# batteryCharger.net
KiCad netlist of a schematic drawn in EAGLE
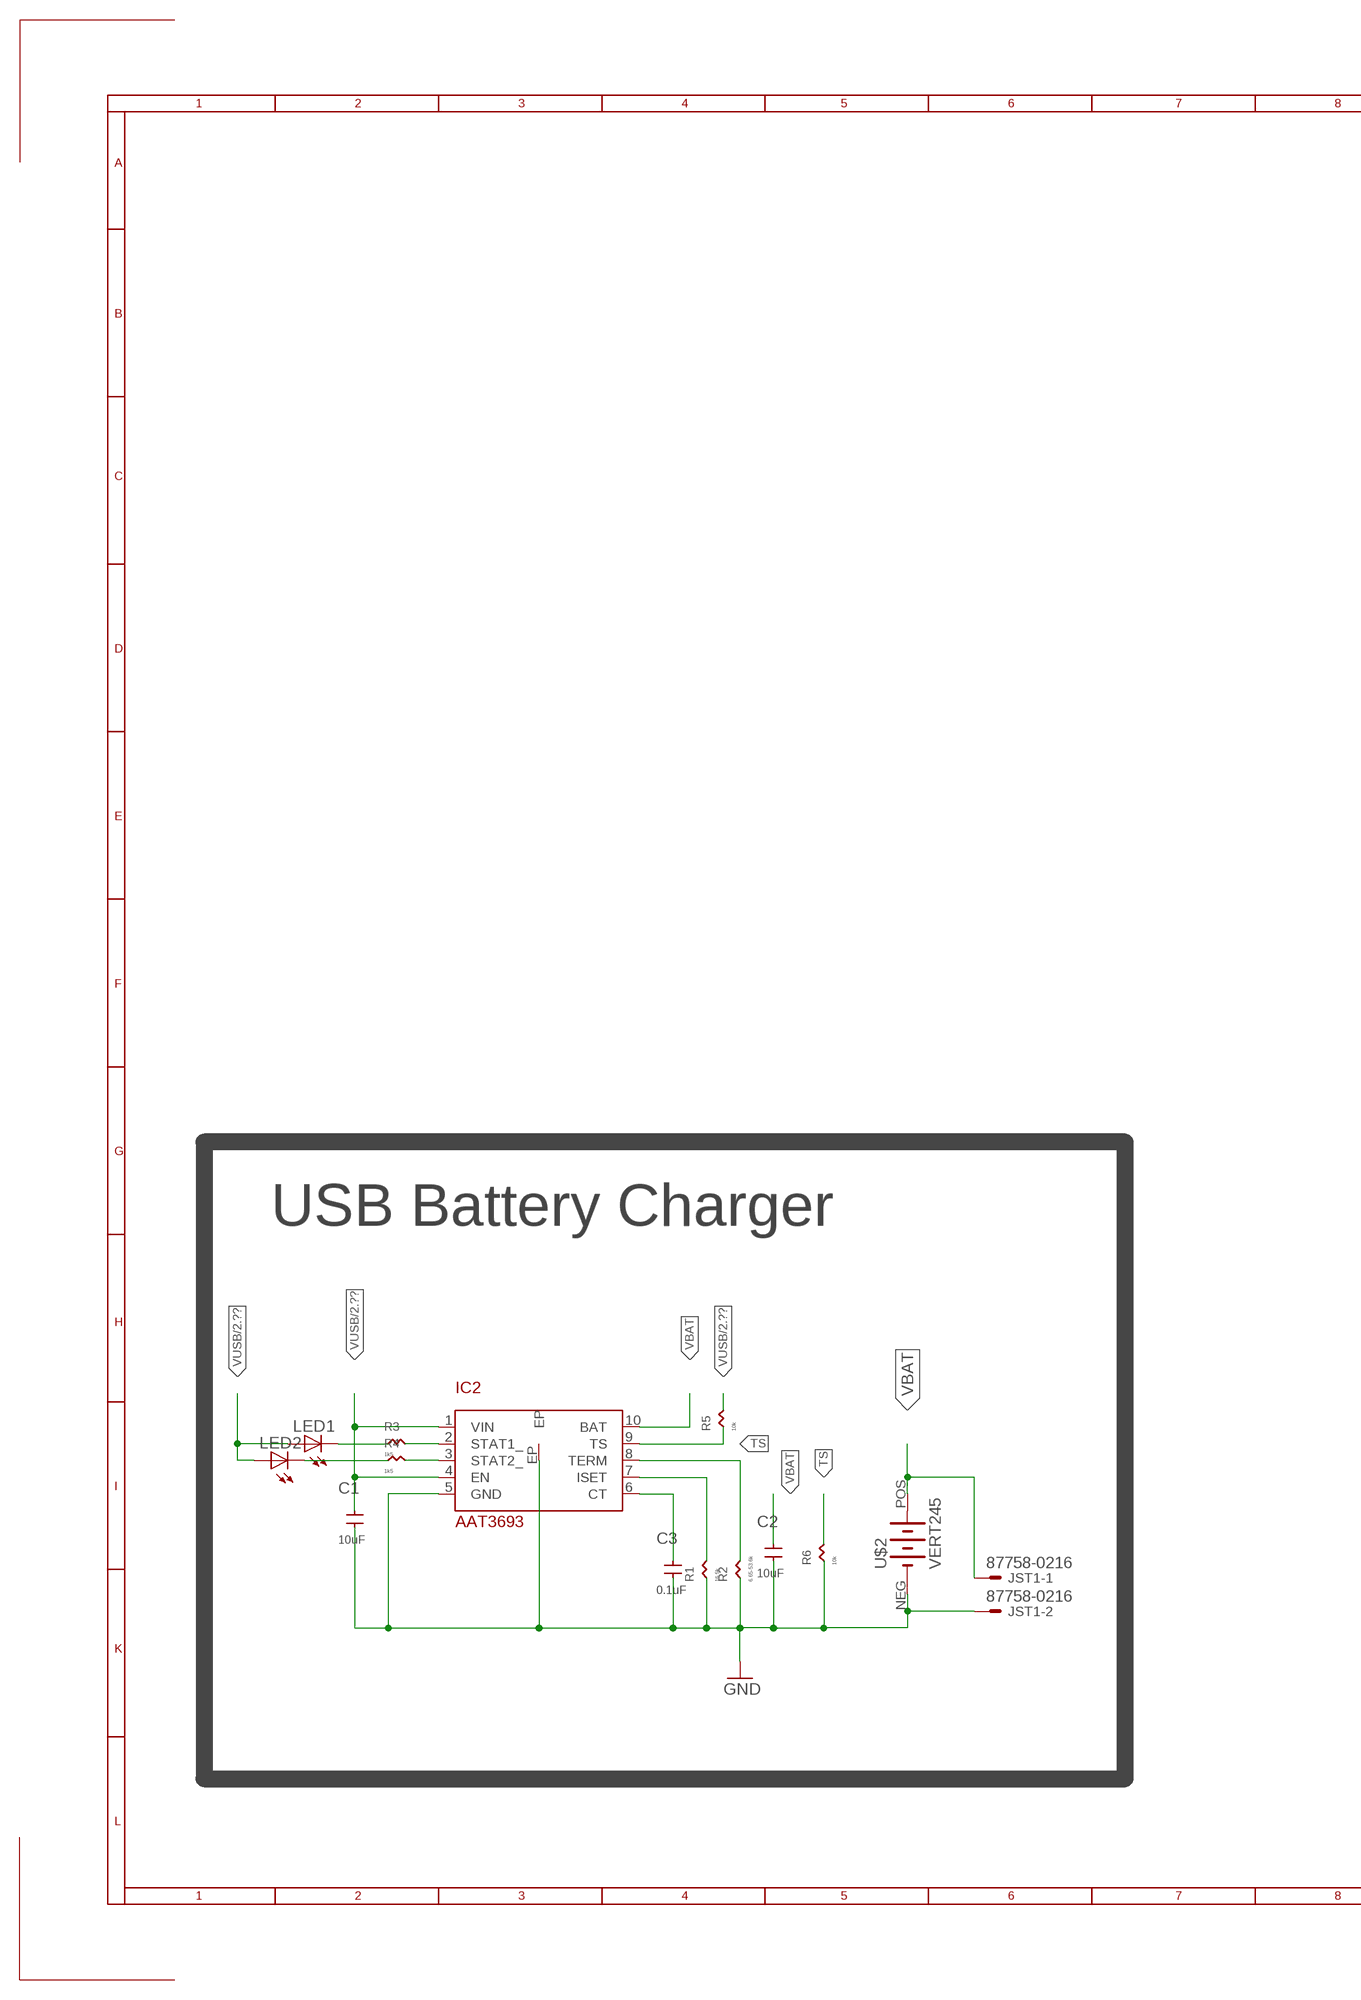
[diagram p0: schematic, sheet 1, part 1 of 2]
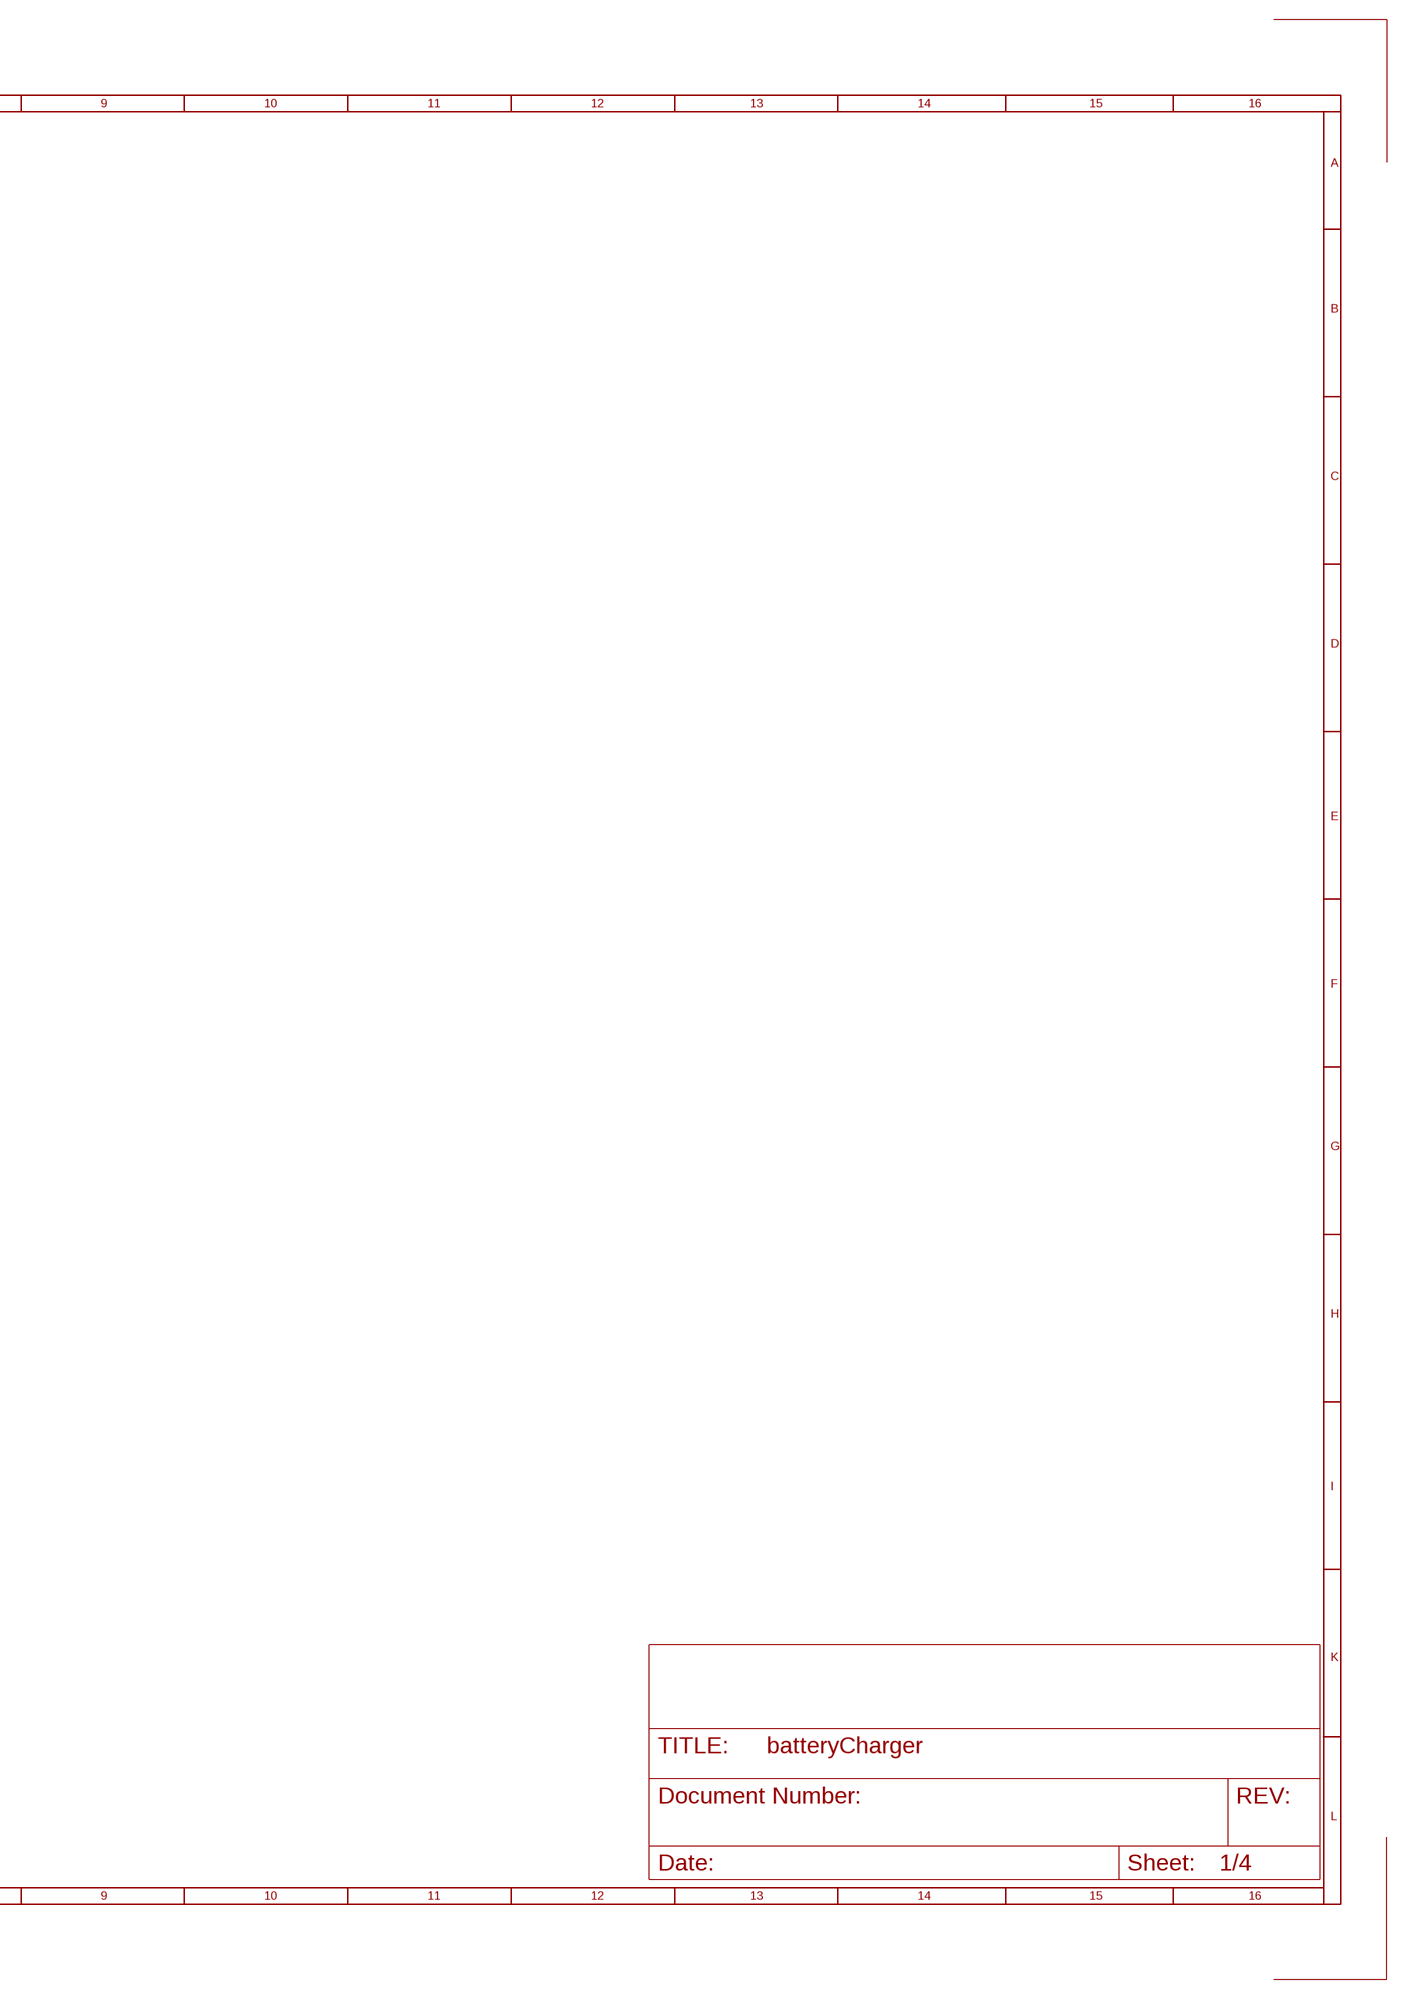
[diagram p1: schematic, sheet 1, part 2 of 2]
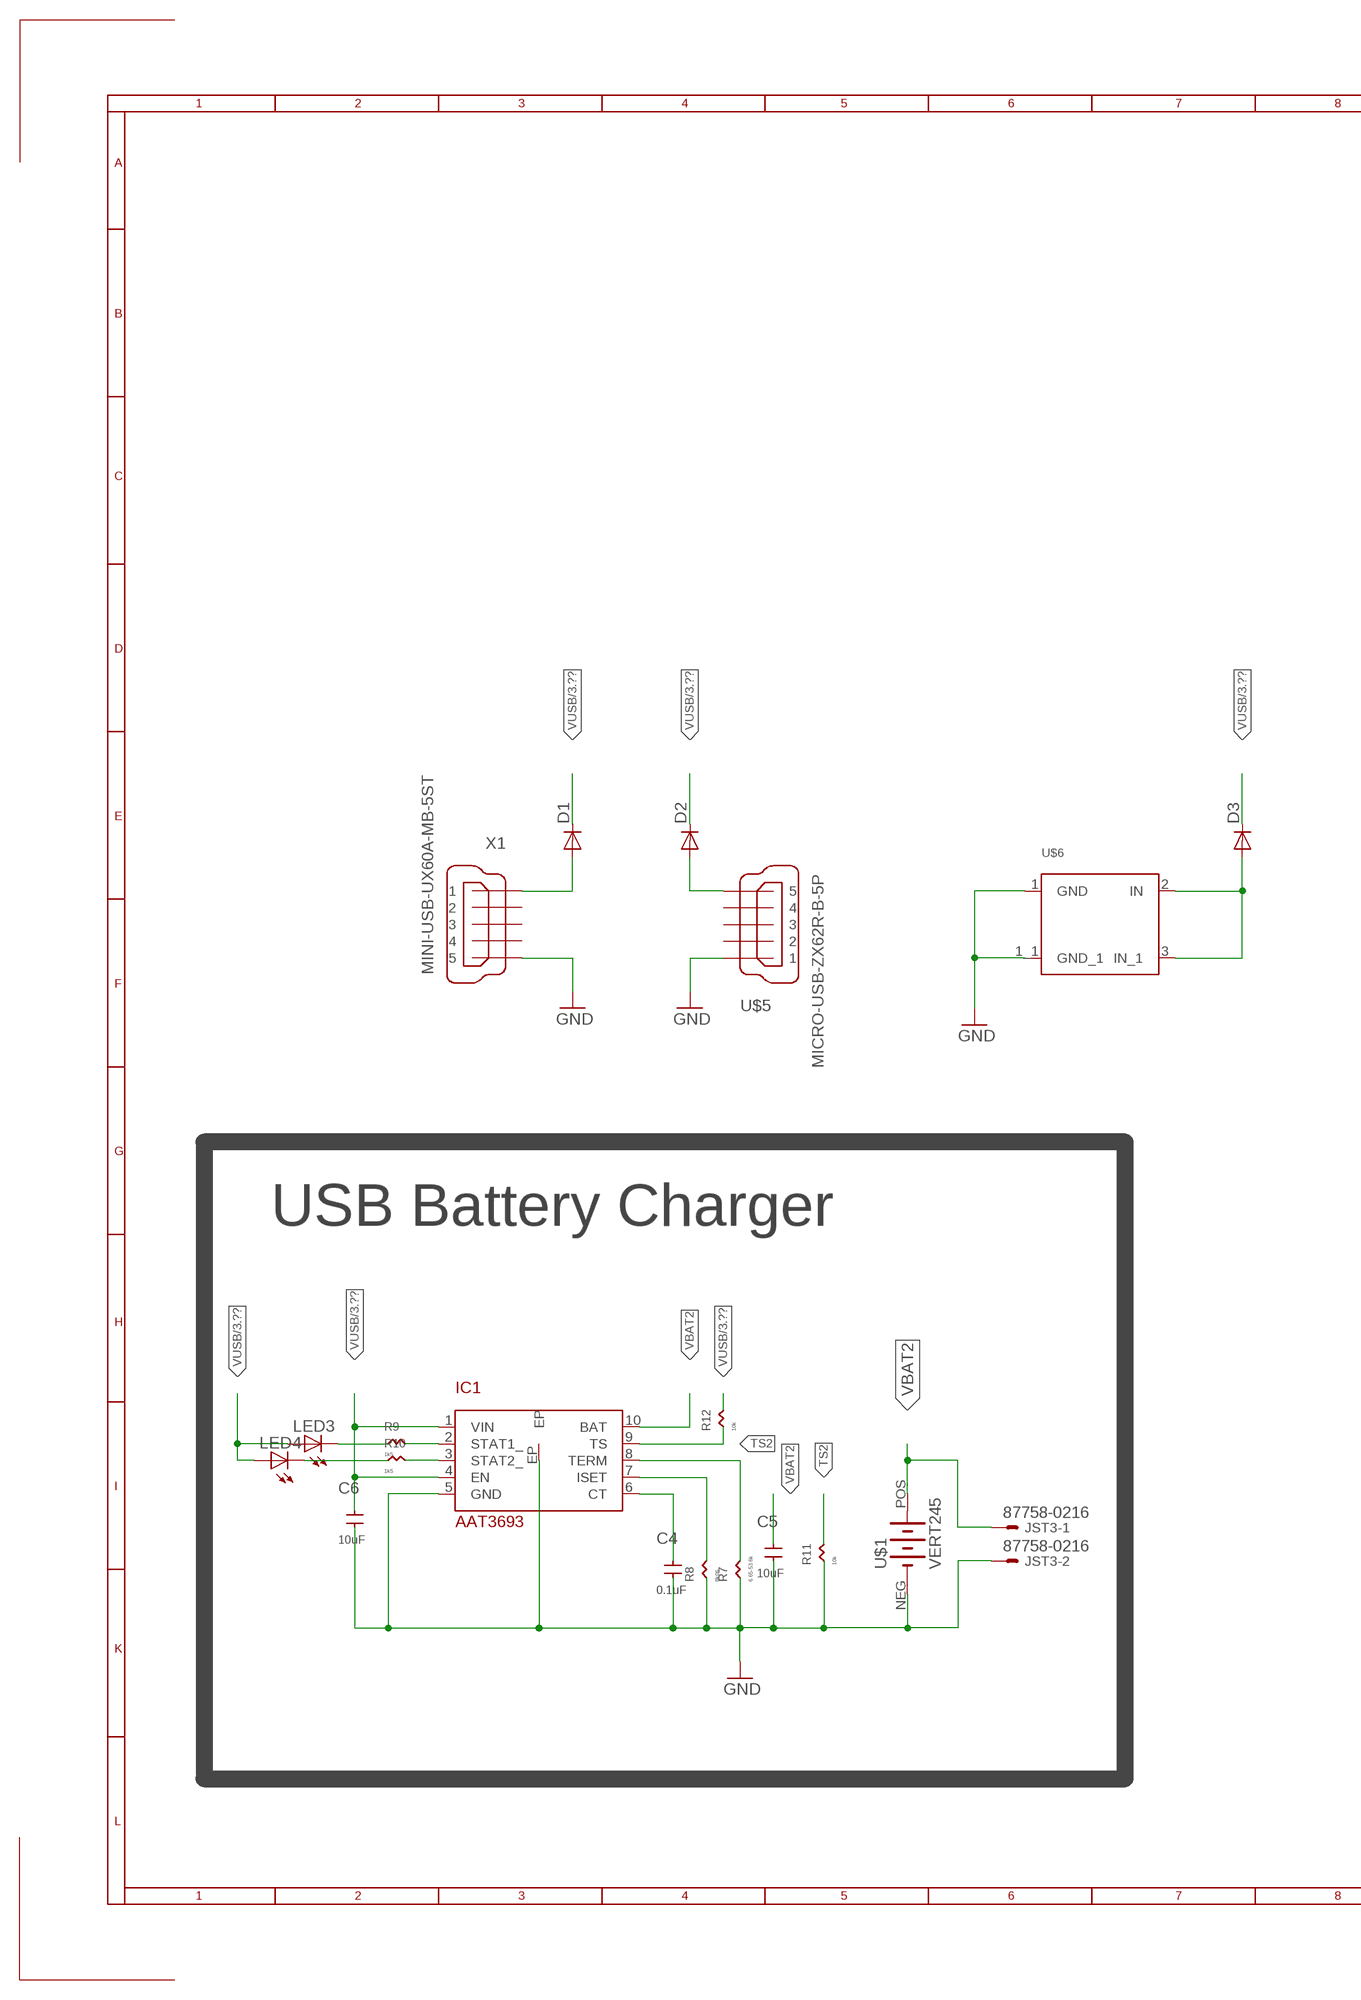
[diagram p2: schematic, sheet 2, part 1 of 2]
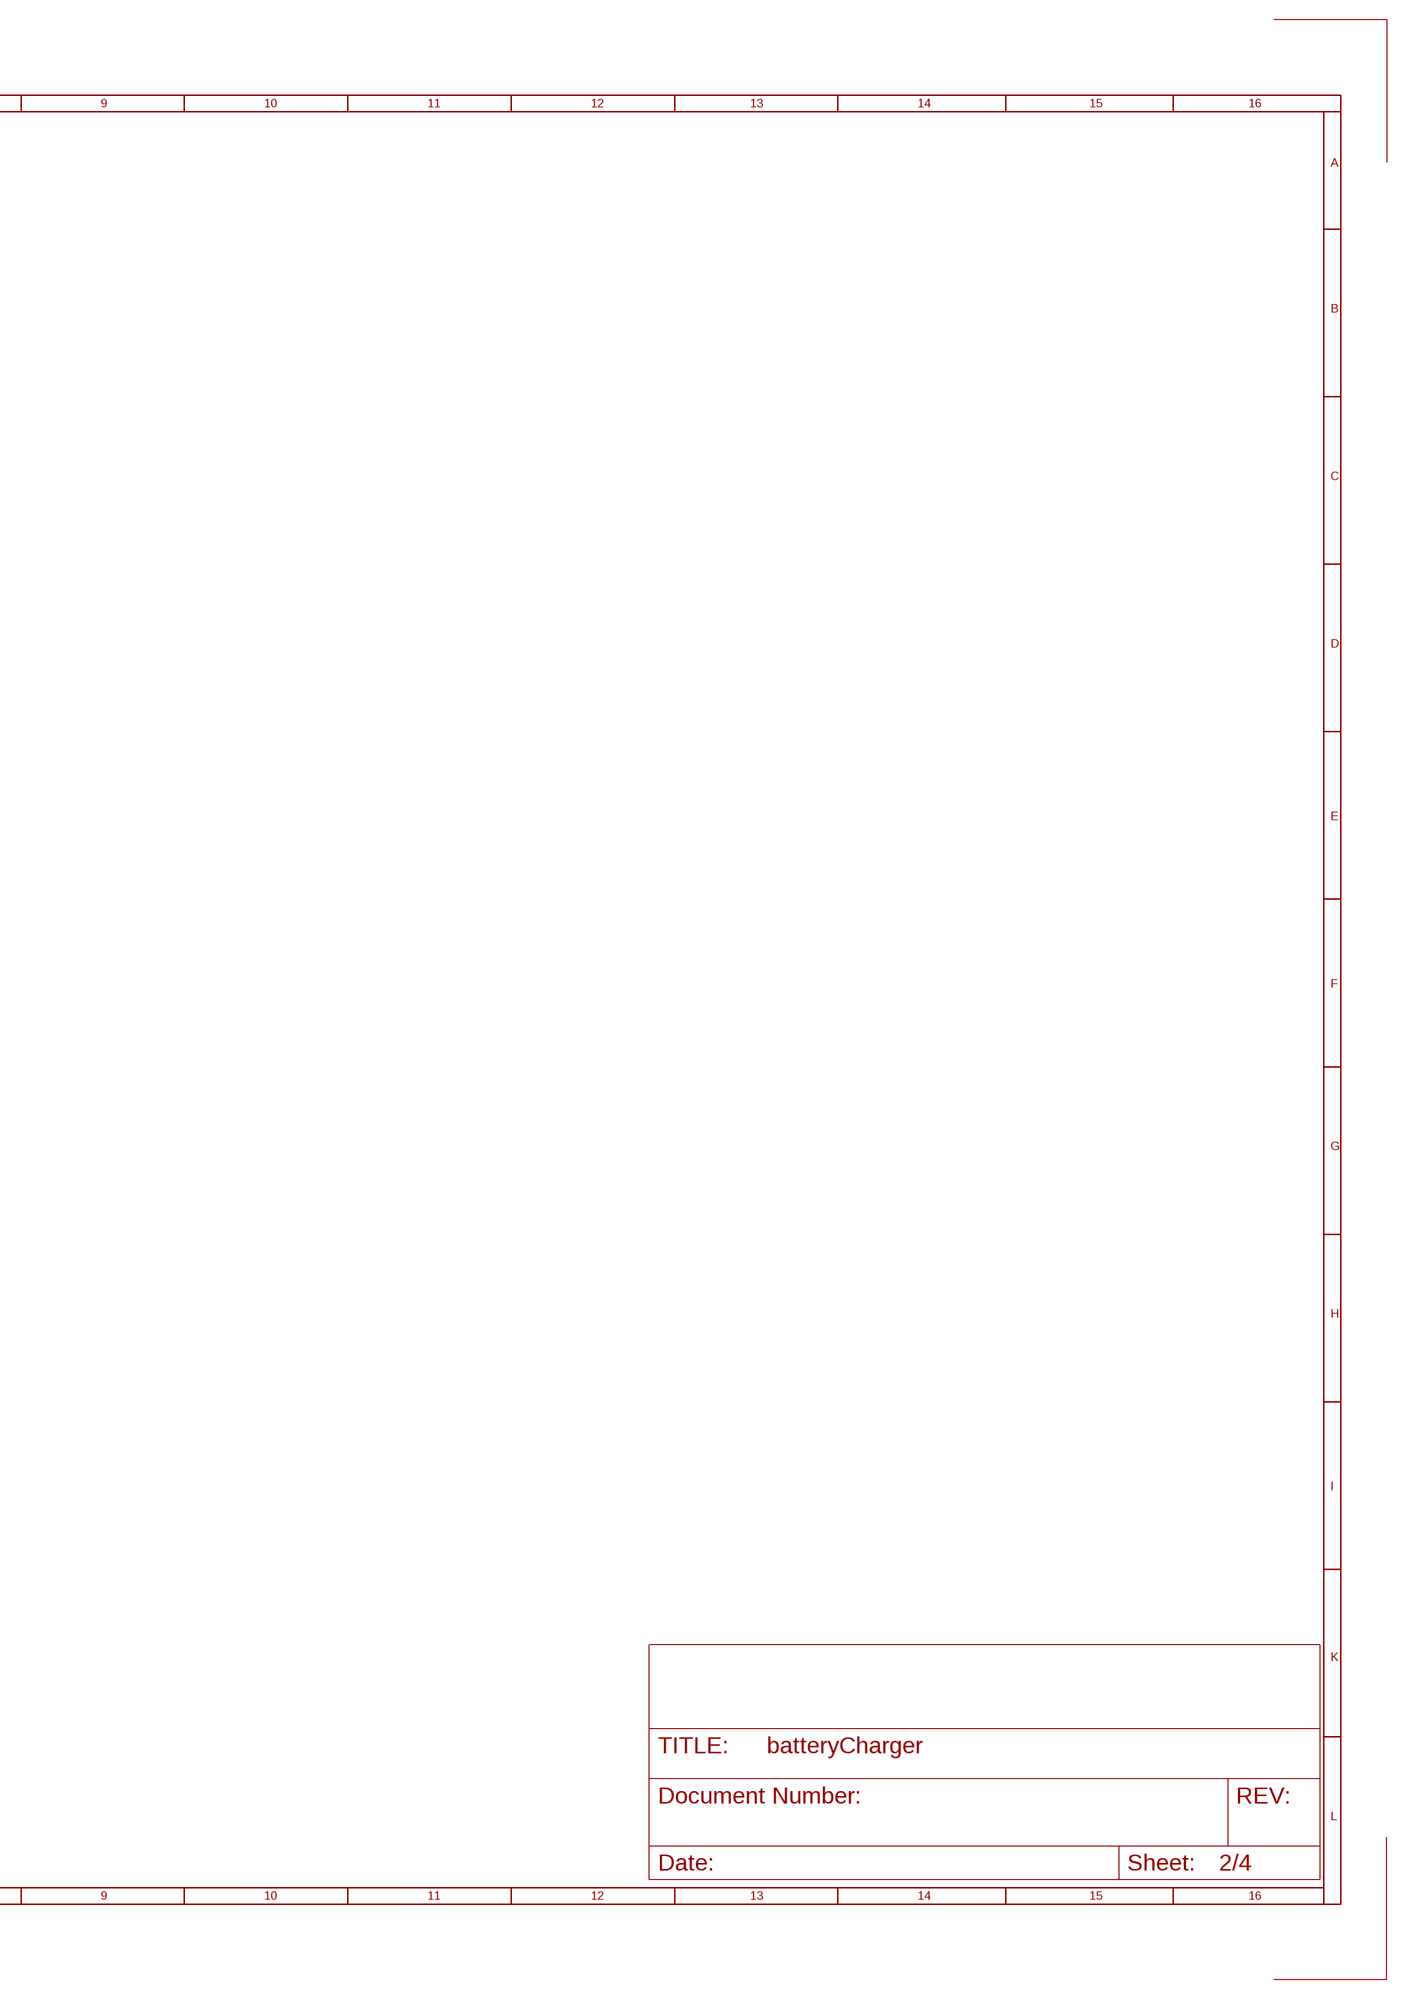
[diagram p3: schematic, sheet 2, part 2 of 2]
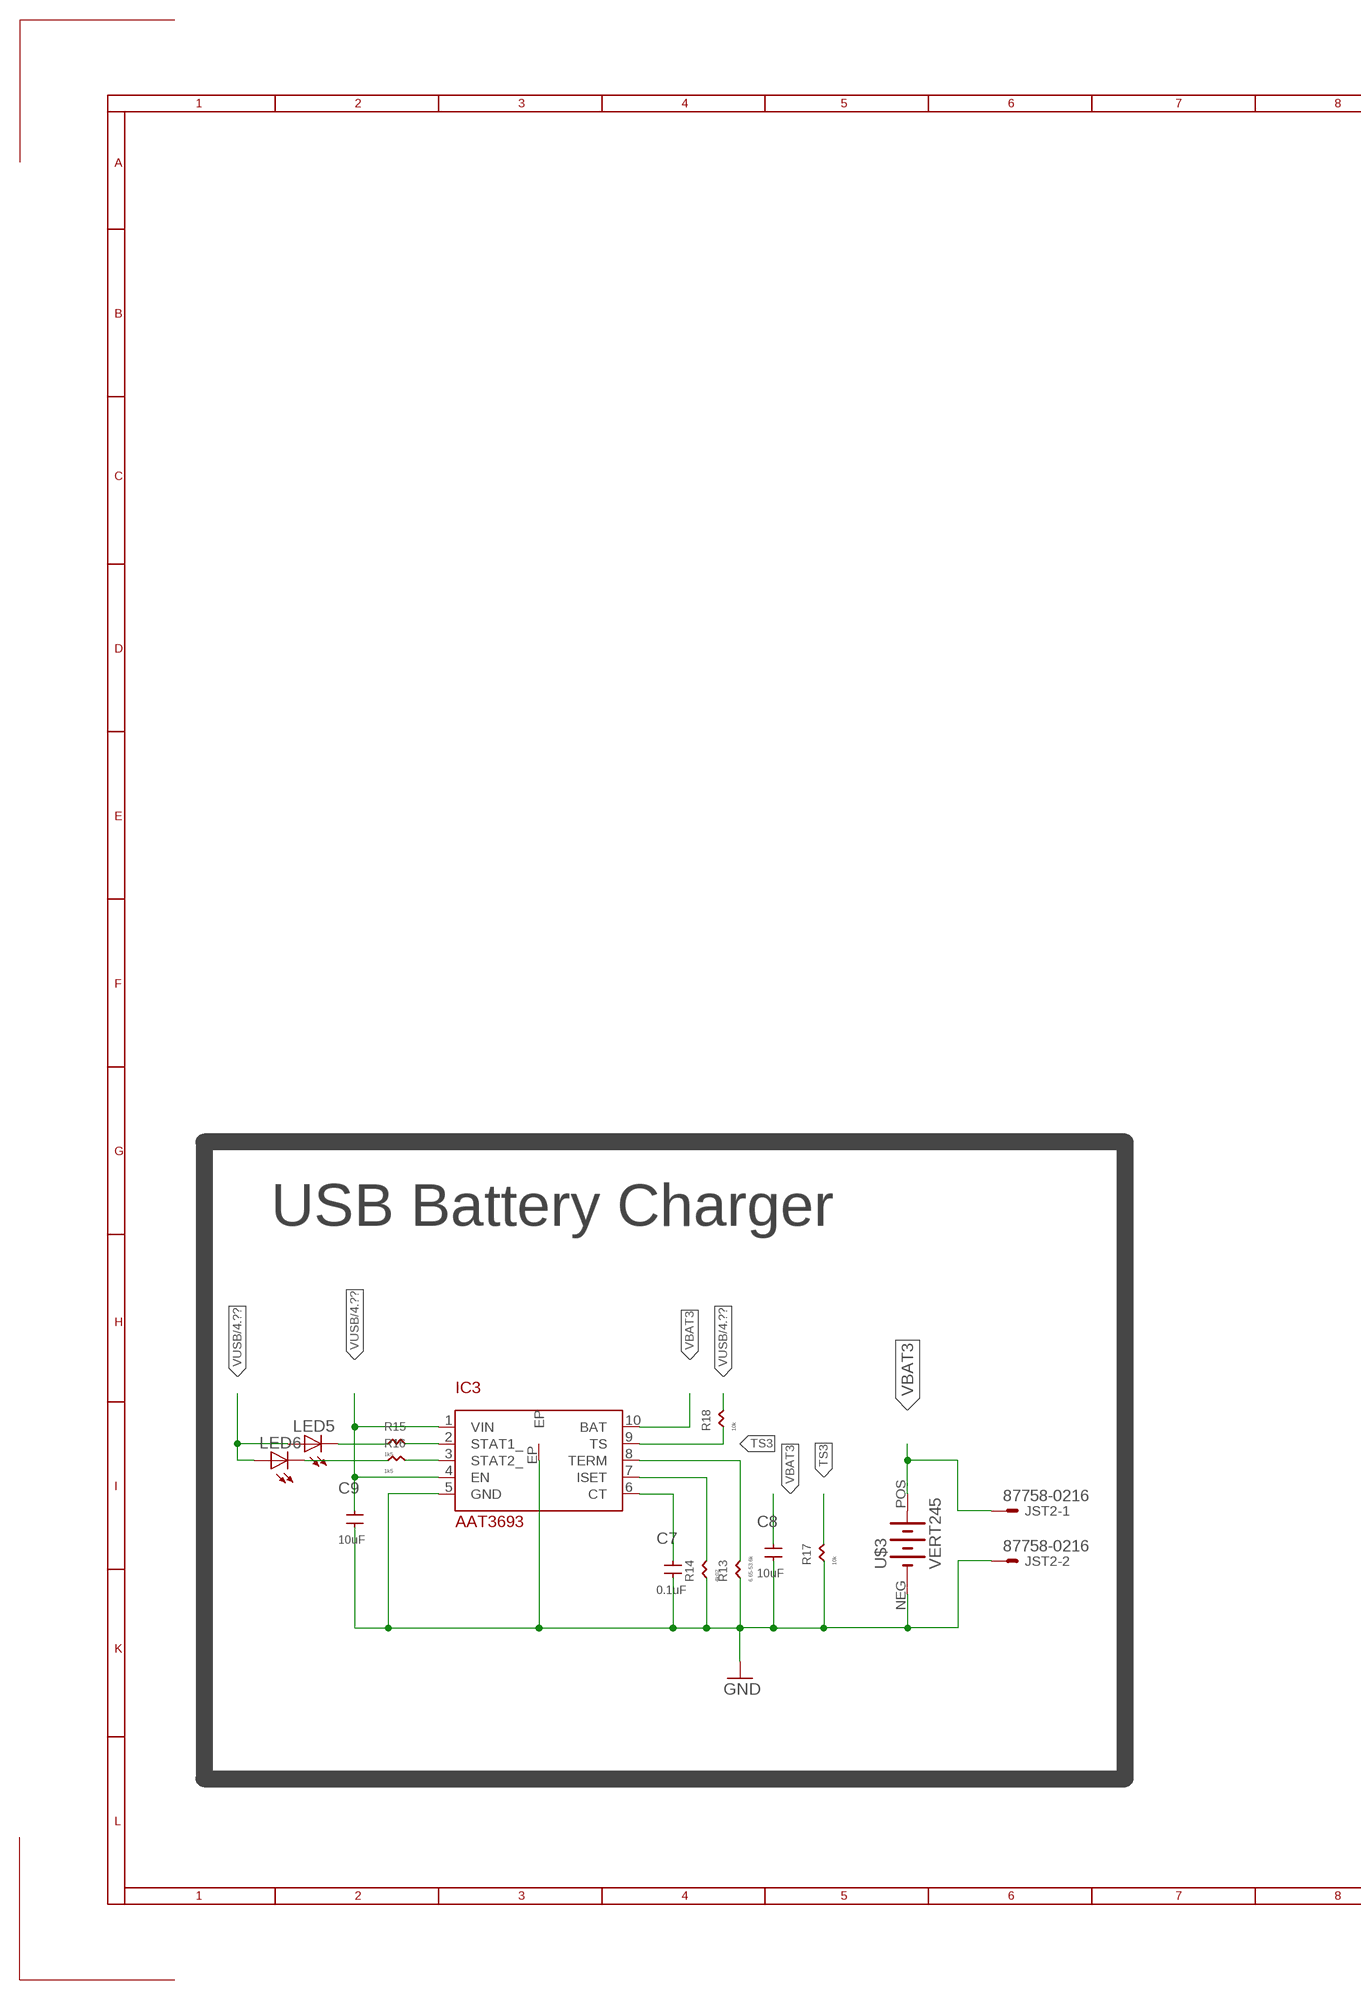
[diagram p4: schematic, sheet 3, part 1 of 2]
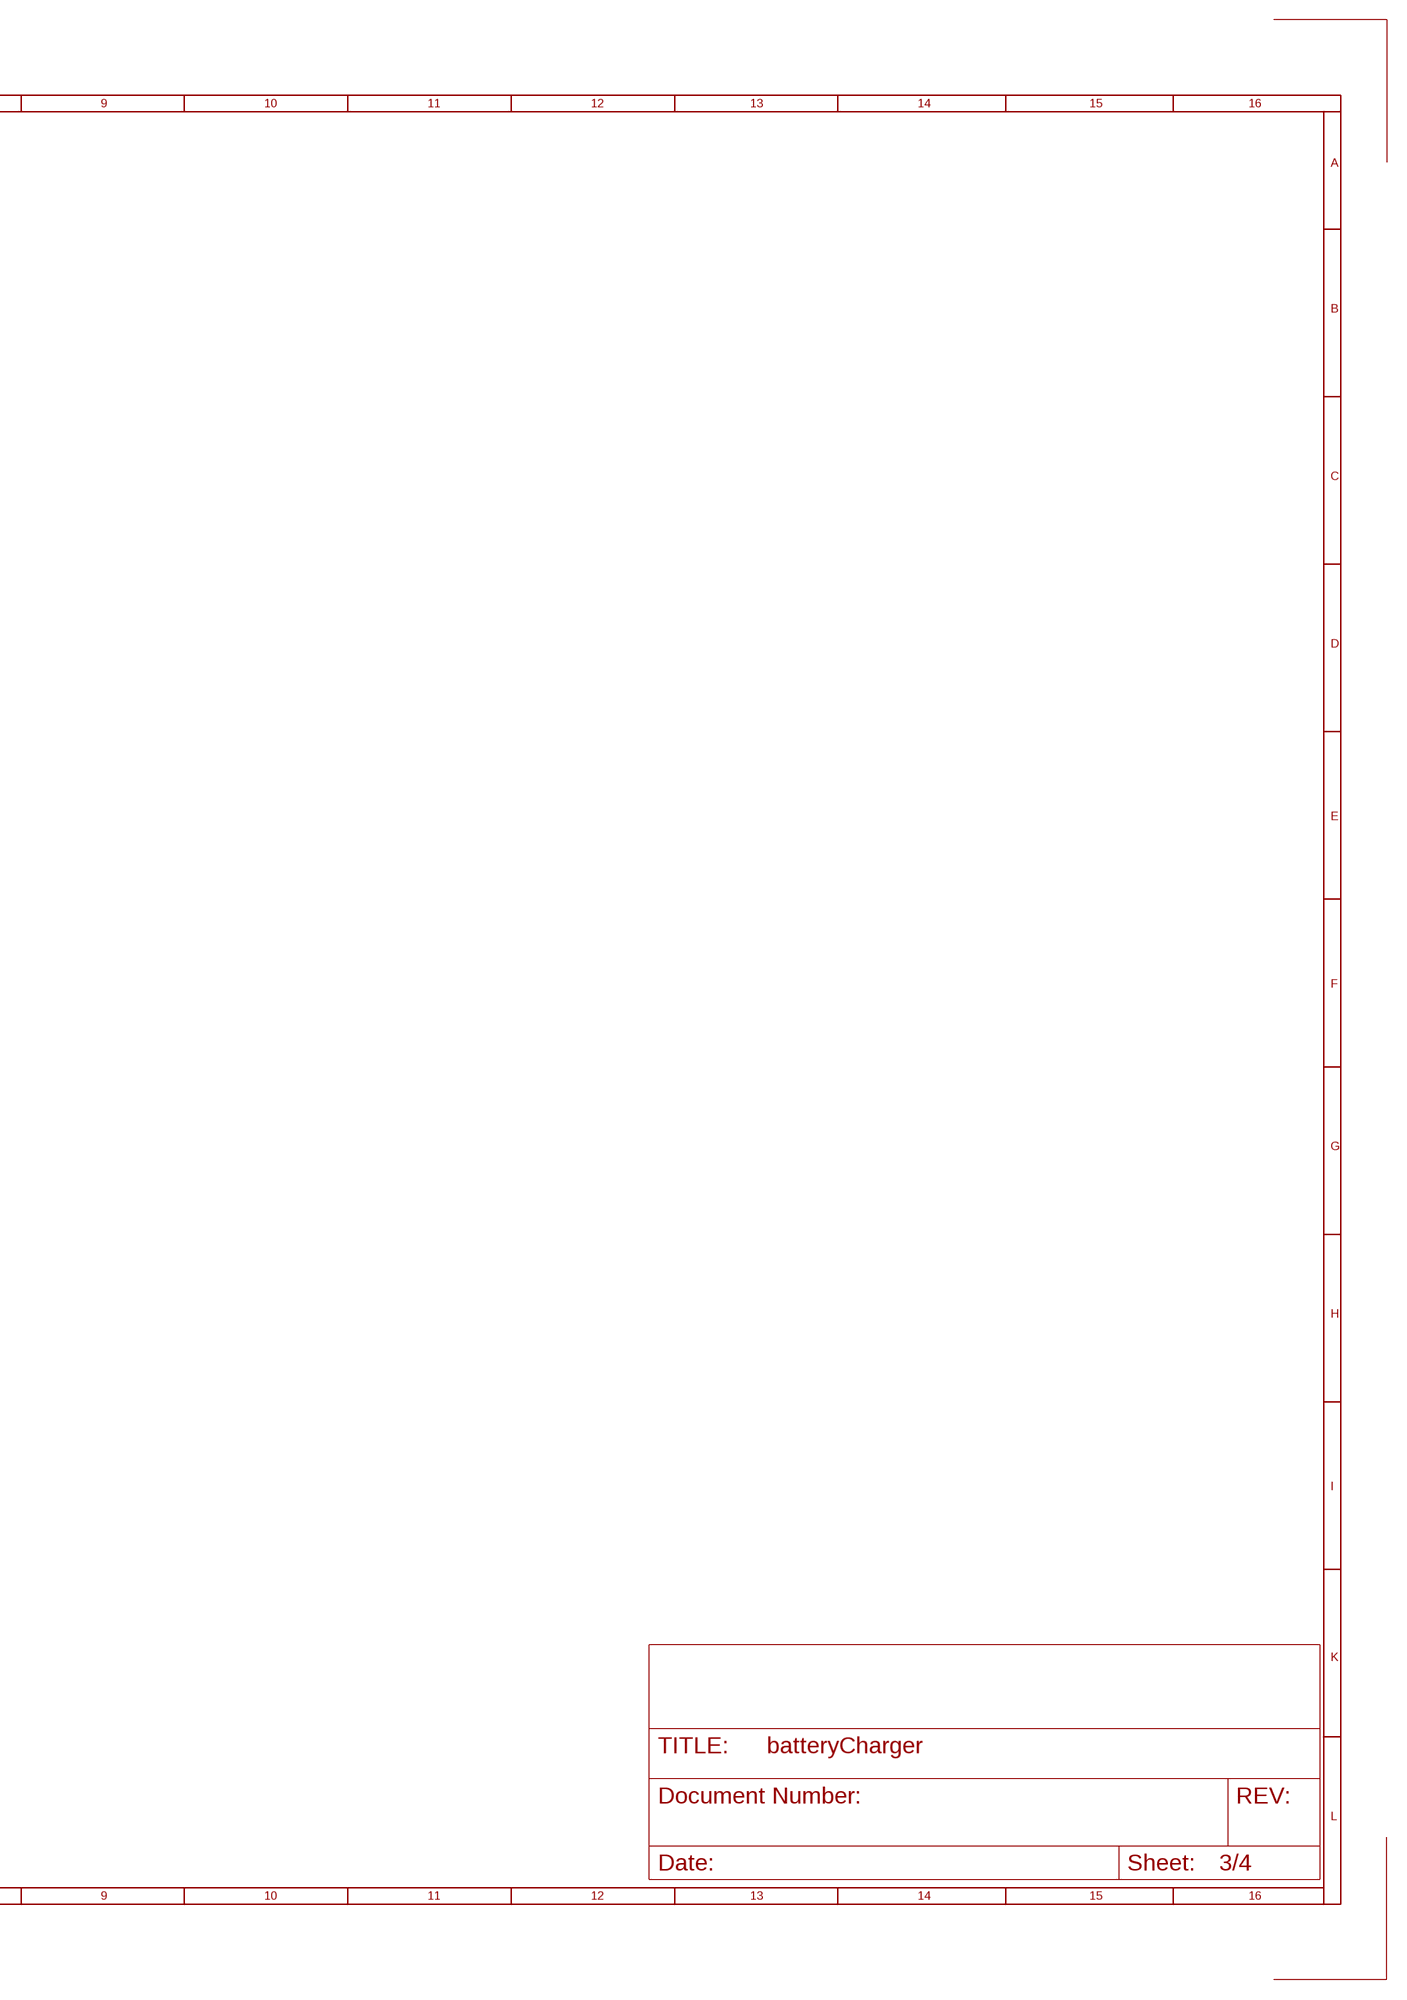
[diagram p5: schematic, sheet 3, part 2 of 2]
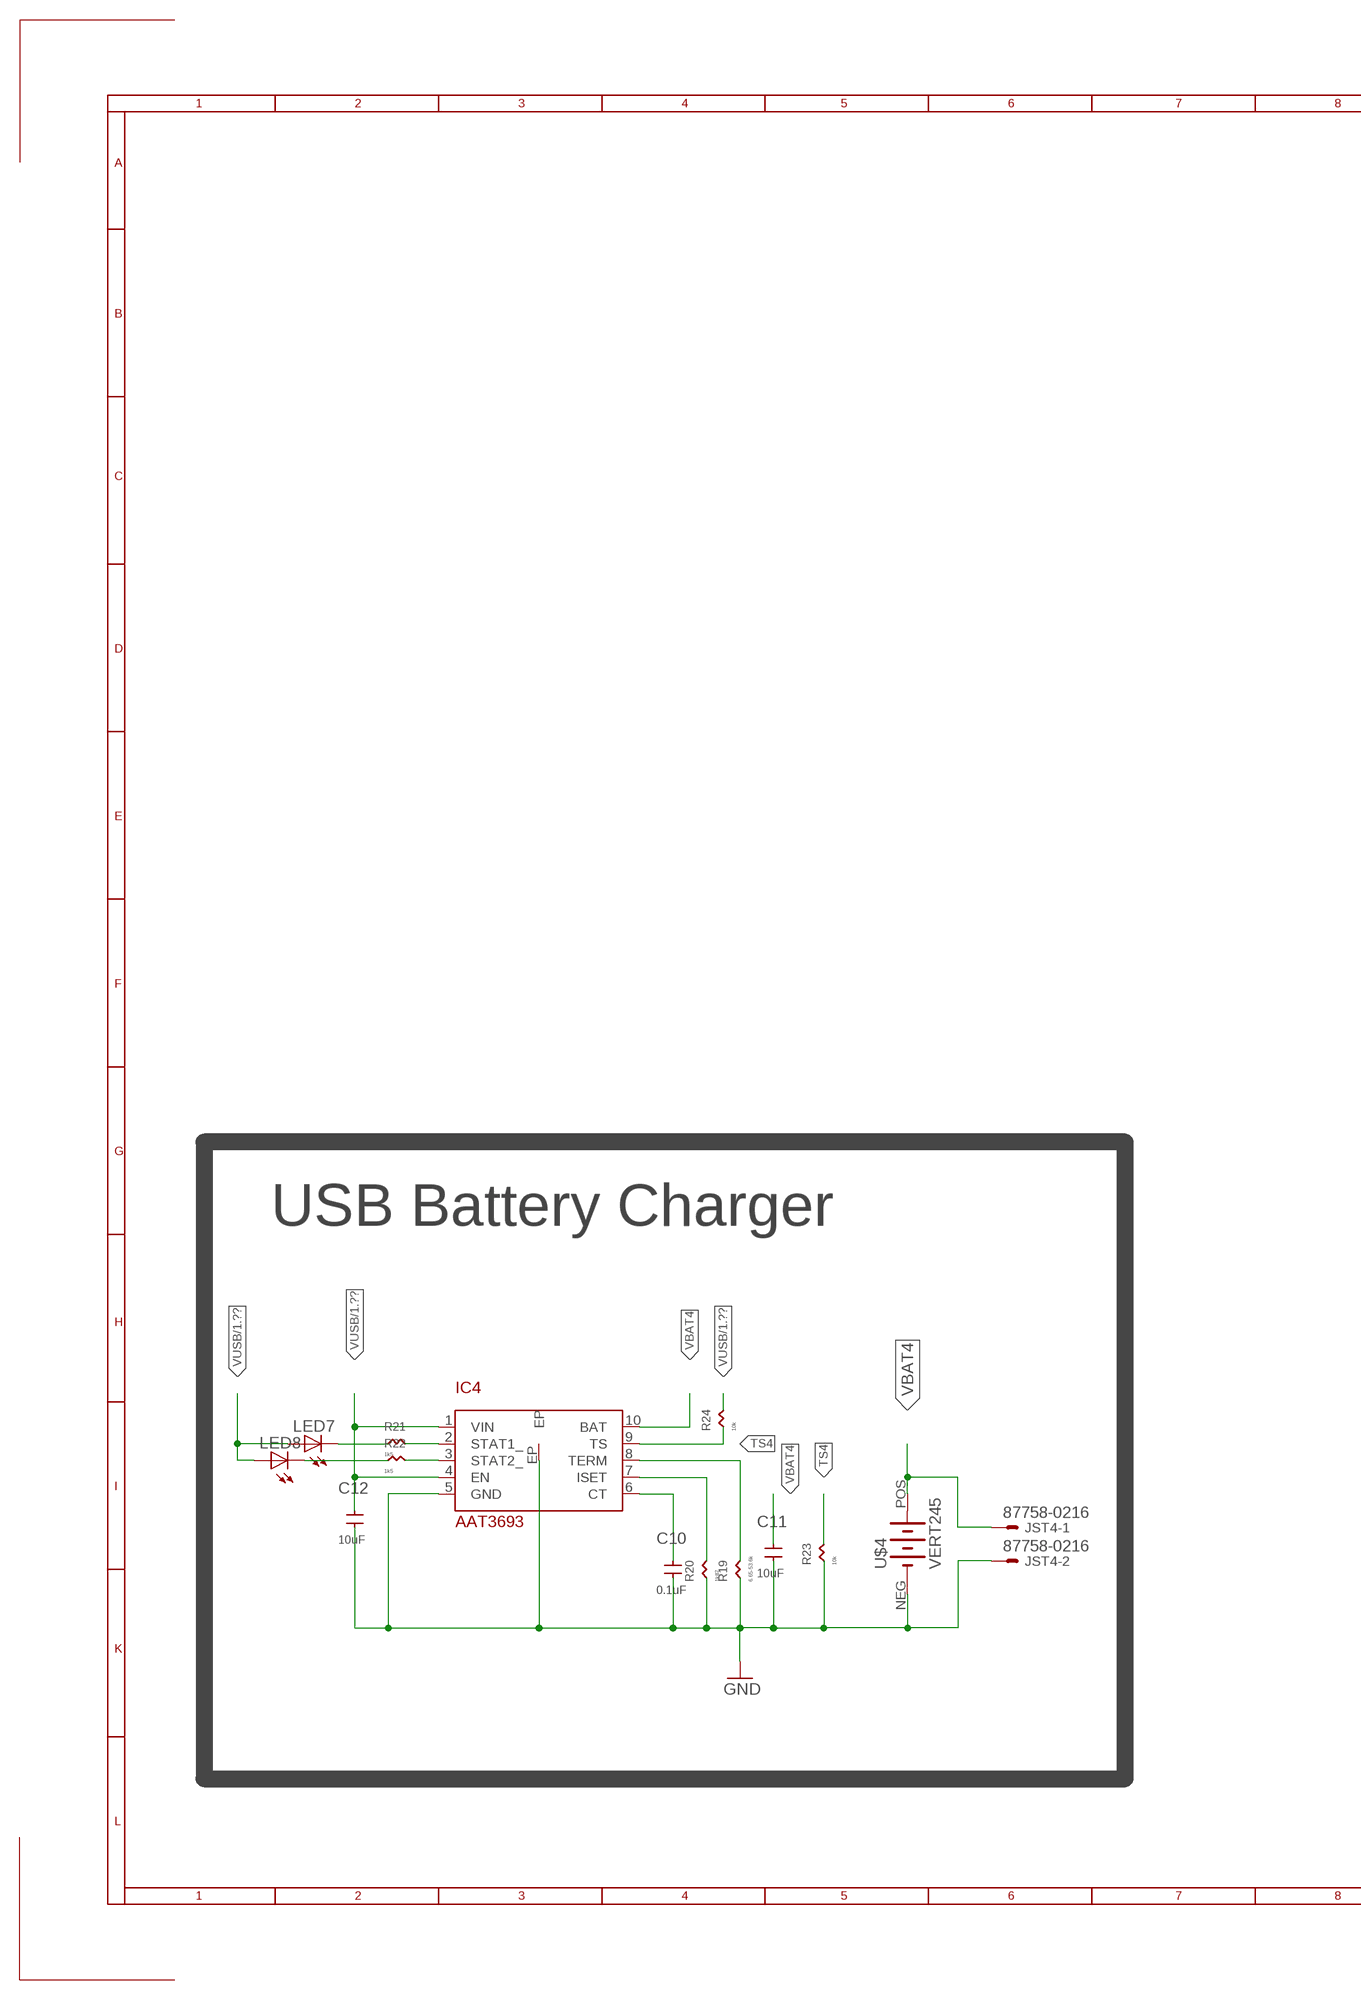
[diagram p6: schematic, sheet 4, part 1 of 2]
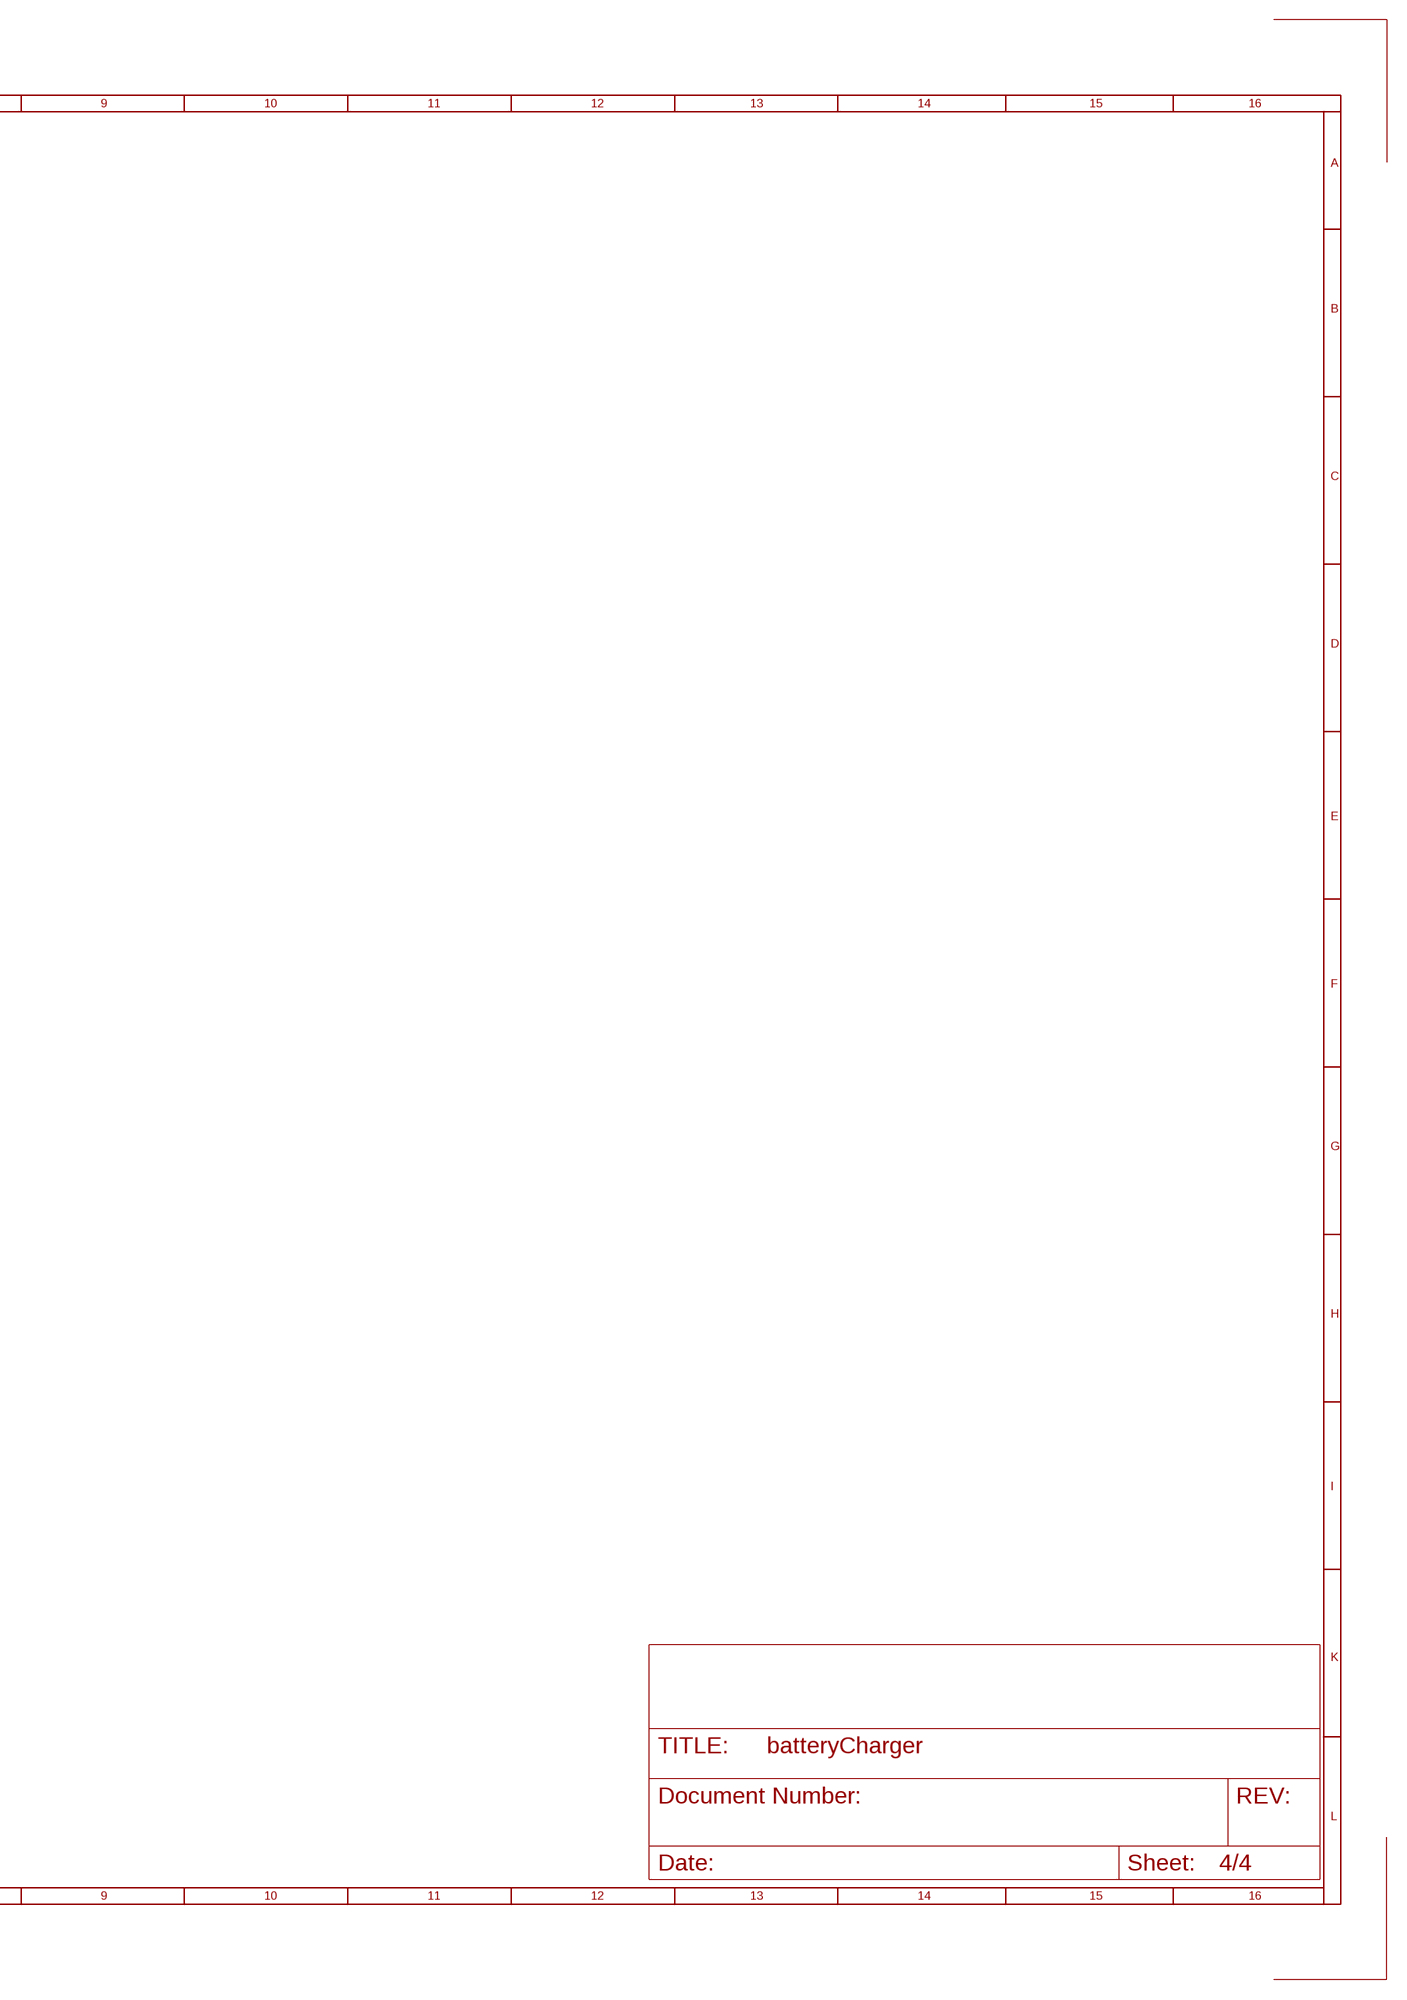
[diagram p7: schematic, sheet 4, part 2 of 2]

(export (version "E")
  (design (tool "Eeschema 10.0.6"))
  (components
    (comp (ref "C7")
      (value "0.1uF")
      (footprint "eagle-import:C0402")
      (libsource (lib "eagle-import") (part "C-ERC0402"))
    )
    (comp (ref "C8")
      (value "10uF")
      (footprint "eagle-import:C0805")
      (libsource (lib "eagle-import") (part "C-ER"))
    )
    (comp (ref "C9")
      (value "10uF")
      (footprint "eagle-import:C0805")
      (libsource (lib "eagle-import") (part "C-ER"))
    )
    (comp (ref "IC3")
      (value "AAT3693")
      (footprint "eagle-import:AAT3693")
      (libsource (lib "eagle-import") (part "AAT3693"))
    )
    (comp (ref "JST2")
      (value "87758-0216")
      (footprint "eagle-import:87758-0216")
      (libsource (lib "eagle-import") (part "87758-0216"))
    )
    (comp (ref "LED5")
      (value "LEDCHIP-LED0603")
      (footprint "eagle-import:CHIP-LED0603")
      (libsource (lib "eagle-import") (part "LEDCHIP-LED0603"))
    )
    (comp (ref "LED6")
      (value "LEDCHIP-LED0603")
      (footprint "eagle-import:CHIP-LED0603")
      (libsource (lib "eagle-import") (part "LEDCHIP-LED0603"))
    )
    (comp (ref "R13")
      (value "6.65-53.6k")
      (footprint "eagle-import:R0402")
      (libsource (lib "eagle-import") (part "R-ER-TINYR402"))
    )
    (comp (ref "R14")
      (value "4k02")
      (footprint "eagle-import:R0402")
      (libsource (lib "eagle-import") (part "R-ER-TINYR402"))
    )
    (comp (ref "R15")
      (value "1k5")
      (footprint "eagle-import:R0402")
      (libsource (lib "eagle-import") (part "R-ER-TINYR402"))
    )
    (comp (ref "R16")
      (value "1k5")
      (footprint "eagle-import:R0402")
      (libsource (lib "eagle-import") (part "R-ER-TINYR402"))
    )
    (comp (ref "R17")
      (value "10k")
      (footprint "eagle-import:R0402")
      (libsource (lib "eagle-import") (part "R-ER-TINYR402"))
    )
    (comp (ref "R18")
      (value "10k")
      (footprint "eagle-import:R0402")
      (libsource (lib "eagle-import") (part "R-ER-TINYR402"))
    )
    (comp (ref "U$3")
      (value "VERT245")
      (footprint "eagle-import:VERT245")
      (libsource (lib "eagle-import") (part "VERT245"))
    )
    (comp (ref "C4")
      (value "0.1uF")
      (footprint "eagle-import:C0402")
      (libsource (lib "eagle-import") (part "C-ERC0402"))
    )
    (comp (ref "C5")
      (value "10uF")
      (footprint "eagle-import:C0805")
      (libsource (lib "eagle-import") (part "C-ER"))
    )
    (comp (ref "C6")
      (value "10uF")
      (footprint "eagle-import:C0805")
      (libsource (lib "eagle-import") (part "C-ER"))
    )
    (comp (ref "D1")
      (value "DIODE-SOD323-R")
      (footprint "eagle-import:SOD323-R")
      (libsource (lib "eagle-import") (part "DIODE-SOD323-R"))
    )
    (comp (ref "D2")
      (value "DIODE-SOD323-R")
      (footprint "eagle-import:SOD323-R")
      (libsource (lib "eagle-import") (part "DIODE-SOD323-R"))
    )
    (comp (ref "D3")
      (value "DIODE-SOD323-R")
      (footprint "eagle-import:SOD323-R")
      (libsource (lib "eagle-import") (part "DIODE-SOD323-R"))
    )
    (comp (ref "IC1")
      (value "AAT3693")
      (footprint "eagle-import:AAT3693")
      (libsource (lib "eagle-import") (part "AAT3693"))
    )
    (comp (ref "JST3")
      (value "87758-0216")
      (footprint "eagle-import:87758-0216")
      (libsource (lib "eagle-import") (part "87758-0216"))
    )
    (comp (ref "LED3")
      (value "LEDCHIP-LED0603")
      (footprint "eagle-import:CHIP-LED0603")
      (libsource (lib "eagle-import") (part "LEDCHIP-LED0603"))
    )
    (comp (ref "LED4")
      (value "LEDCHIP-LED0603")
      (footprint "eagle-import:CHIP-LED0603")
      (libsource (lib "eagle-import") (part "LEDCHIP-LED0603"))
    )
    (comp (ref "R7")
      (value "6.65-53.6k")
      (footprint "eagle-import:R0402")
      (libsource (lib "eagle-import") (part "R-ER-TINYR402"))
    )
    (comp (ref "R8")
      (value "8k06")
      (footprint "eagle-import:R0402")
      (libsource (lib "eagle-import") (part "R-ER-TINYR402"))
    )
    (comp (ref "R9")
      (value "1k5")
      (footprint "eagle-import:R0402")
      (libsource (lib "eagle-import") (part "R-ER-TINYR402"))
    )
    (comp (ref "R10")
      (value "1k5")
      (footprint "eagle-import:R0402")
      (libsource (lib "eagle-import") (part "R-ER-TINYR402"))
    )
    (comp (ref "R11")
      (value "10k")
      (footprint "eagle-import:R0402")
      (libsource (lib "eagle-import") (part "R-ER-TINYR402"))
    )
    (comp (ref "R12")
      (value "10k")
      (footprint "eagle-import:R0402")
      (libsource (lib "eagle-import") (part "R-ER-TINYR402"))
    )
    (comp (ref "U$1")
      (value "VERT245")
      (footprint "eagle-import:VERT245")
      (libsource (lib "eagle-import") (part "VERT245"))
    )
    (comp (ref "U$5")
      (value "MICRO-USB-ZX62R-B-5P")
      (footprint "eagle-import:ZX62R-B-5P")
      (libsource (lib "eagle-import") (part "MICRO-USB-ZX62R-B-5P"))
    )
    (comp (ref "U$6")
      (value "PJ-002A_SMT")
      (footprint "eagle-import:PJ-002A_SMT")
      (libsource (lib "eagle-import") (part "PJ-002A_SMT"))
    )
    (comp (ref "X1")
      (value "MINI-USB-UX60A-MB-5ST")
      (footprint "eagle-import:UX60A-MB-5ST")
      (libsource (lib "eagle-import") (part "MINI-USB-UX60A-MB-5ST"))
    )
    (comp (ref "C10")
      (value "0.1uF")
      (footprint "eagle-import:C0402")
      (libsource (lib "eagle-import") (part "C-ERC0402"))
    )
    (comp (ref "C11")
      (value "10uF")
      (footprint "eagle-import:C0805")
      (libsource (lib "eagle-import") (part "C-ER"))
    )
    (comp (ref "C12")
      (value "10uF")
      (footprint "eagle-import:C0805")
      (libsource (lib "eagle-import") (part "C-ER"))
    )
    (comp (ref "IC4")
      (value "AAT3693")
      (footprint "eagle-import:AAT3693")
      (libsource (lib "eagle-import") (part "AAT3693"))
    )
    (comp (ref "JST4")
      (value "87758-0216")
      (footprint "eagle-import:87758-0216")
      (libsource (lib "eagle-import") (part "87758-0216"))
    )
    (comp (ref "LED7")
      (value "LEDCHIP-LED0603")
      (footprint "eagle-import:CHIP-LED0603")
      (libsource (lib "eagle-import") (part "LEDCHIP-LED0603"))
    )
    (comp (ref "LED8")
      (value "LEDCHIP-LED0603")
      (footprint "eagle-import:CHIP-LED0603")
      (libsource (lib "eagle-import") (part "LEDCHIP-LED0603"))
    )
    (comp (ref "R19")
      (value "6.65-53.6k")
      (footprint "eagle-import:R0402")
      (libsource (lib "eagle-import") (part "R-ER-TINYR402"))
    )
    (comp (ref "R20")
      (value "1k87")
      (footprint "eagle-import:R0402")
      (libsource (lib "eagle-import") (part "R-ER-TINYR402"))
    )
    (comp (ref "R21")
      (value "1k5")
      (footprint "eagle-import:R0402")
      (libsource (lib "eagle-import") (part "R-ER-TINYR402"))
    )
    (comp (ref "R22")
      (value "1k5")
      (footprint "eagle-import:R0402")
      (libsource (lib "eagle-import") (part "R-ER-TINYR402"))
    )
    (comp (ref "R23")
      (value "10k")
      (footprint "eagle-import:R0402")
      (libsource (lib "eagle-import") (part "R-ER-TINYR402"))
    )
    (comp (ref "R24")
      (value "10k")
      (footprint "eagle-import:R0402")
      (libsource (lib "eagle-import") (part "R-ER-TINYR402"))
    )
    (comp (ref "U$4")
      (value "VERT245")
      (footprint "eagle-import:VERT245")
      (libsource (lib "eagle-import") (part "VERT245"))
    )
    (comp (ref "C1")
      (value "10uF")
      (footprint "eagle-import:C0805")
      (libsource (lib "eagle-import") (part "C-ER"))
    )
    (comp (ref "C2")
      (value "10uF")
      (footprint "eagle-import:C0805")
      (libsource (lib "eagle-import") (part "C-ER"))
    )
    (comp (ref "C3")
      (value "0.1uF")
      (footprint "eagle-import:C0402")
      (libsource (lib "eagle-import") (part "C-ERC0402"))
    )
    (comp (ref "IC2")
      (value "AAT3693")
      (footprint "eagle-import:AAT3693")
      (libsource (lib "eagle-import") (part "AAT3693"))
    )
    (comp (ref "JST1")
      (value "87758-0216")
      (footprint "eagle-import:87758-0216")
      (libsource (lib "eagle-import") (part "87758-0216"))
    )
    (comp (ref "LED1")
      (value "LEDCHIP-LED0603")
      (footprint "eagle-import:CHIP-LED0603")
      (libsource (lib "eagle-import") (part "LEDCHIP-LED0603"))
    )
    (comp (ref "LED2")
      (value "LEDCHIP-LED0603")
      (footprint "eagle-import:CHIP-LED0603")
      (libsource (lib "eagle-import") (part "LEDCHIP-LED0603"))
    )
    (comp (ref "R1")
      (value "16.5k")
      (footprint "eagle-import:R0402")
      (libsource (lib "eagle-import") (part "R-ER-TINYR402"))
    )
    (comp (ref "R2")
      (value "6.65-53.6k")
      (footprint "eagle-import:R0402")
      (libsource (lib "eagle-import") (part "R-ER-TINYR402"))
    )
    (comp (ref "R3")
      (value "1k5")
      (footprint "eagle-import:R0402")
      (libsource (lib "eagle-import") (part "R-ER-TINYR402"))
    )
    (comp (ref "R4")
      (value "1k5")
      (footprint "eagle-import:R0402")
      (libsource (lib "eagle-import") (part "R-ER-TINYR402"))
    )
    (comp (ref "R5")
      (value "10k")
      (footprint "eagle-import:R0402")
      (libsource (lib "eagle-import") (part "R-ER-TINYR402"))
    )
    (comp (ref "R6")
      (value "10k")
      (footprint "eagle-import:R0402")
      (libsource (lib "eagle-import") (part "R-ER-TINYR402"))
    )
    (comp (ref "U$2")
      (value "VERT245")
      (footprint "eagle-import:VERT245")
      (libsource (lib "eagle-import") (part "VERT245"))
    )
  )
  (nets
    (net (code "1") (name "GND") (class "Default")
      (node (ref "C1") (pin "1") (pinfunction "P$1_1") (pintype "bidirectional"))
      (node (ref "C10") (pin "1") (pinfunction "P$1_1") (pintype "bidirectional"))
      (node (ref "C11") (pin "1") (pinfunction "P$1_1") (pintype "bidirectional"))
      (node (ref "C12") (pin "1") (pinfunction "P$1_1") (pintype "bidirectional"))
      (node (ref "C2") (pin "1") (pinfunction "P$1_1") (pintype "bidirectional"))
      (node (ref "C3") (pin "1") (pinfunction "P$1_1") (pintype "bidirectional"))
      (node (ref "C4") (pin "1") (pinfunction "P$1_1") (pintype "bidirectional"))
      (node (ref "C5") (pin "1") (pinfunction "P$1_1") (pintype "bidirectional"))
      (node (ref "C6") (pin "1") (pinfunction "P$1_1") (pintype "bidirectional"))
      (node (ref "C7") (pin "1") (pinfunction "P$1_1") (pintype "bidirectional"))
      (node (ref "C8") (pin "1") (pinfunction "P$1_1") (pintype "bidirectional"))
      (node (ref "C9") (pin "1") (pinfunction "P$1_1") (pintype "bidirectional"))
      (node (ref "IC1") (pin "5") (pinfunction "GND_5") (pintype "bidirectional"))
      (node (ref "IC1") (pin "EP") (pinfunction "EP_EP") (pintype "bidirectional"))
      (node (ref "IC2") (pin "5") (pinfunction "GND_5") (pintype "bidirectional"))
      (node (ref "IC2") (pin "EP") (pinfunction "EP_EP") (pintype "bidirectional"))
      (node (ref "IC3") (pin "5") (pinfunction "GND_5") (pintype "bidirectional"))
      (node (ref "IC3") (pin "EP") (pinfunction "EP_EP") (pintype "bidirectional"))
      (node (ref "IC4") (pin "5") (pinfunction "GND_5") (pintype "bidirectional"))
      (node (ref "IC4") (pin "EP") (pinfunction "EP_EP") (pintype "bidirectional"))
      (node (ref "JST1") (pin "2") (pinfunction "S_2") (pintype "passive"))
      (node (ref "JST2") (pin "2") (pinfunction "S_2") (pintype "passive"))
      (node (ref "JST3") (pin "2") (pinfunction "S_2") (pintype "passive"))
      (node (ref "JST4") (pin "2") (pinfunction "S_2") (pintype "passive"))
      (node (ref "R1") (pin "1") (pinfunction "P$1_1") (pintype "bidirectional"))
      (node (ref "R11") (pin "1") (pinfunction "P$1_1") (pintype "bidirectional"))
      (node (ref "R13") (pin "1") (pinfunction "P$1_1") (pintype "bidirectional"))
      (node (ref "R14") (pin "1") (pinfunction "P$1_1") (pintype "bidirectional"))
      (node (ref "R17") (pin "1") (pinfunction "P$1_1") (pintype "bidirectional"))
      (node (ref "R19") (pin "1") (pinfunction "P$1_1") (pintype "bidirectional"))
      (node (ref "R2") (pin "1") (pinfunction "P$1_1") (pintype "bidirectional"))
      (node (ref "R20") (pin "1") (pinfunction "P$1_1") (pintype "bidirectional"))
      (node (ref "R23") (pin "1") (pinfunction "P$1_1") (pintype "bidirectional"))
      (node (ref "R6") (pin "1") (pinfunction "P$1_1") (pintype "bidirectional"))
      (node (ref "R7") (pin "1") (pinfunction "P$1_1") (pintype "bidirectional"))
      (node (ref "R8") (pin "1") (pinfunction "P$1_1") (pintype "bidirectional"))
      (node (ref "U$1") (pin "NEG") (pinfunction "-_NEG") (pintype "passive"))
      (node (ref "U$2") (pin "NEG") (pinfunction "-_NEG") (pintype "passive"))
      (node (ref "U$3") (pin "NEG") (pinfunction "-_NEG") (pintype "passive"))
      (node (ref "U$4") (pin "NEG") (pinfunction "-_NEG") (pintype "passive"))
      (node (ref "U$5") (pin "1") (pinfunction "1_1") (pintype "input"))
      (node (ref "U$6") (pin "1") (pinfunction "GND_1") (pintype "bidirectional"))
      (node (ref "U$6") (pin "1_1") (pinfunction "GND_1_1_1") (pintype "bidirectional"))
      (node (ref "X1") (pin "5") (pinfunction "5_5") (pintype "input"))
    )
    (net (code "2") (name "Net-(C3-P$2)") (class "Default")
      (node (ref "C3") (pin "2") (pinfunction "P$2_2") (pintype "bidirectional"))
      (node (ref "IC2") (pin "6") (pinfunction "CT_6") (pintype "bidirectional"))
    )
    (net (code "3") (name "Net-(C4-P$2)") (class "Default")
      (node (ref "C4") (pin "2") (pinfunction "P$2_2") (pintype "bidirectional"))
      (node (ref "IC1") (pin "6") (pinfunction "CT_6") (pintype "bidirectional"))
    )
    (net (code "4") (name "Net-(C7-P$2)") (class "Default")
      (node (ref "C7") (pin "2") (pinfunction "P$2_2") (pintype "bidirectional"))
      (node (ref "IC3") (pin "6") (pinfunction "CT_6") (pintype "bidirectional"))
    )
    (net (code "5") (name "Net-(C10-P$2)") (class "Default")
      (node (ref "C10") (pin "2") (pinfunction "P$2_2") (pintype "bidirectional"))
      (node (ref "IC4") (pin "6") (pinfunction "CT_6") (pintype "bidirectional"))
    )
    (net (code "6") (name "Net-(D1-PadA)") (class "Default")
      (node (ref "D1") (pin "A") (pinfunction "A_A") (pintype "passive"))
      (node (ref "X1") (pin "1") (pinfunction "1_1") (pintype "input"))
    )
    (net (code "7") (name "Net-(D2-PadA)") (class "Default")
      (node (ref "D2") (pin "A") (pinfunction "A_A") (pintype "passive"))
      (node (ref "U$5") (pin "5") (pinfunction "5_5") (pintype "input"))
    )
    (net (code "8") (name "Net-(IC1-ISET)") (class "Default")
      (node (ref "IC1") (pin "7") (pinfunction "ISET_7") (pintype "bidirectional"))
      (node (ref "R8") (pin "2") (pinfunction "P$2_2") (pintype "bidirectional"))
    )
    (net (code "9") (name "Net-(IC1-STAT1_)") (class "Default")
      (node (ref "IC1") (pin "2") (pinfunction "STAT1__2") (pintype "bidirectional"))
      (node (ref "R9") (pin "2") (pinfunction "P$2_2") (pintype "bidirectional"))
    )
    (net (code "10") (name "Net-(IC1-STAT2_)") (class "Default")
      (node (ref "IC1") (pin "3") (pinfunction "STAT2__3") (pintype "bidirectional"))
      (node (ref "R10") (pin "2") (pinfunction "P$2_2") (pintype "bidirectional"))
    )
    (net (code "11") (name "Net-(IC1-TERM)") (class "Default")
      (node (ref "IC1") (pin "8") (pinfunction "TERM_8") (pintype "bidirectional"))
      (node (ref "R7") (pin "2") (pinfunction "P$2_2") (pintype "bidirectional"))
    )
    (net (code "12") (name "Net-(IC2-ISET)") (class "Default")
      (node (ref "IC2") (pin "7") (pinfunction "ISET_7") (pintype "bidirectional"))
      (node (ref "R1") (pin "2") (pinfunction "P$2_2") (pintype "bidirectional"))
    )
    (net (code "13") (name "Net-(IC2-STAT1_)") (class "Default")
      (node (ref "IC2") (pin "2") (pinfunction "STAT1__2") (pintype "bidirectional"))
      (node (ref "R3") (pin "2") (pinfunction "P$2_2") (pintype "bidirectional"))
    )
    (net (code "14") (name "Net-(IC2-STAT2_)") (class "Default")
      (node (ref "IC2") (pin "3") (pinfunction "STAT2__3") (pintype "bidirectional"))
      (node (ref "R4") (pin "2") (pinfunction "P$2_2") (pintype "bidirectional"))
    )
    (net (code "15") (name "Net-(IC2-TERM)") (class "Default")
      (node (ref "IC2") (pin "8") (pinfunction "TERM_8") (pintype "bidirectional"))
      (node (ref "R2") (pin "2") (pinfunction "P$2_2") (pintype "bidirectional"))
    )
    (net (code "16") (name "Net-(IC3-ISET)") (class "Default")
      (node (ref "IC3") (pin "7") (pinfunction "ISET_7") (pintype "bidirectional"))
      (node (ref "R14") (pin "2") (pinfunction "P$2_2") (pintype "bidirectional"))
    )
    (net (code "17") (name "Net-(IC3-STAT1_)") (class "Default")
      (node (ref "IC3") (pin "2") (pinfunction "STAT1__2") (pintype "bidirectional"))
      (node (ref "R15") (pin "2") (pinfunction "P$2_2") (pintype "bidirectional"))
    )
    (net (code "18") (name "Net-(IC3-STAT2_)") (class "Default")
      (node (ref "IC3") (pin "3") (pinfunction "STAT2__3") (pintype "bidirectional"))
      (node (ref "R16") (pin "2") (pinfunction "P$2_2") (pintype "bidirectional"))
    )
    (net (code "19") (name "Net-(IC3-TERM)") (class "Default")
      (node (ref "IC3") (pin "8") (pinfunction "TERM_8") (pintype "bidirectional"))
      (node (ref "R13") (pin "2") (pinfunction "P$2_2") (pintype "bidirectional"))
    )
    (net (code "20") (name "Net-(IC4-ISET)") (class "Default")
      (node (ref "IC4") (pin "7") (pinfunction "ISET_7") (pintype "bidirectional"))
      (node (ref "R20") (pin "2") (pinfunction "P$2_2") (pintype "bidirectional"))
    )
    (net (code "21") (name "Net-(IC4-STAT1_)") (class "Default")
      (node (ref "IC4") (pin "2") (pinfunction "STAT1__2") (pintype "bidirectional"))
      (node (ref "R21") (pin "2") (pinfunction "P$2_2") (pintype "bidirectional"))
    )
    (net (code "22") (name "Net-(IC4-STAT2_)") (class "Default")
      (node (ref "IC4") (pin "3") (pinfunction "STAT2__3") (pintype "bidirectional"))
      (node (ref "R22") (pin "2") (pinfunction "P$2_2") (pintype "bidirectional"))
    )
    (net (code "23") (name "Net-(IC4-TERM)") (class "Default")
      (node (ref "IC4") (pin "8") (pinfunction "TERM_8") (pintype "bidirectional"))
      (node (ref "R19") (pin "2") (pinfunction "P$2_2") (pintype "bidirectional"))
    )
    (net (code "24") (name "Net-(R3-P$1)") (class "Default")
      (node (ref "LED1") (pin "C") (pinfunction "C_C") (pintype "passive"))
      (node (ref "R3") (pin "1") (pinfunction "P$1_1") (pintype "bidirectional"))
    )
    (net (code "25") (name "Net-(R4-P$1)") (class "Default")
      (node (ref "LED2") (pin "C") (pinfunction "C_C") (pintype "passive"))
      (node (ref "R4") (pin "1") (pinfunction "P$1_1") (pintype "bidirectional"))
    )
    (net (code "26") (name "Net-(R9-P$1)") (class "Default")
      (node (ref "LED3") (pin "C") (pinfunction "C_C") (pintype "passive"))
      (node (ref "R9") (pin "1") (pinfunction "P$1_1") (pintype "bidirectional"))
    )
    (net (code "27") (name "Net-(R10-P$1)") (class "Default")
      (node (ref "LED4") (pin "C") (pinfunction "C_C") (pintype "passive"))
      (node (ref "R10") (pin "1") (pinfunction "P$1_1") (pintype "bidirectional"))
    )
    (net (code "28") (name "Net-(R15-P$1)") (class "Default")
      (node (ref "LED5") (pin "C") (pinfunction "C_C") (pintype "passive"))
      (node (ref "R15") (pin "1") (pinfunction "P$1_1") (pintype "bidirectional"))
    )
    (net (code "29") (name "Net-(R16-P$1)") (class "Default")
      (node (ref "LED6") (pin "C") (pinfunction "C_C") (pintype "passive"))
      (node (ref "R16") (pin "1") (pinfunction "P$1_1") (pintype "bidirectional"))
    )
    (net (code "30") (name "Net-(R21-P$1)") (class "Default")
      (node (ref "LED7") (pin "C") (pinfunction "C_C") (pintype "passive"))
      (node (ref "R21") (pin "1") (pinfunction "P$1_1") (pintype "bidirectional"))
    )
    (net (code "31") (name "Net-(R22-P$1)") (class "Default")
      (node (ref "LED8") (pin "C") (pinfunction "C_C") (pintype "passive"))
      (node (ref "R22") (pin "1") (pinfunction "P$1_1") (pintype "bidirectional"))
    )
    (net (code "32") (name "Net-(U$6-IN)") (class "Default")
      (node (ref "D3") (pin "A") (pinfunction "A_A") (pintype "passive"))
      (node (ref "U$6") (pin "2") (pinfunction "IN_2") (pintype "bidirectional"))
      (node (ref "U$6") (pin "3") (pinfunction "IN_1_3") (pintype "bidirectional"))
    )
    (net (code "33") (name "TS") (class "Default")
      (node (ref "IC2") (pin "9") (pinfunction "TS_9") (pintype "bidirectional"))
      (node (ref "R5") (pin "1") (pinfunction "P$1_1") (pintype "bidirectional"))
      (node (ref "R6") (pin "2") (pinfunction "P$2_2") (pintype "bidirectional"))
    )
    (net (code "34") (name "TS2") (class "Default")
      (node (ref "IC1") (pin "9") (pinfunction "TS_9") (pintype "bidirectional"))
      (node (ref "R11") (pin "2") (pinfunction "P$2_2") (pintype "bidirectional"))
      (node (ref "R12") (pin "1") (pinfunction "P$1_1") (pintype "bidirectional"))
    )
    (net (code "35") (name "TS3") (class "Default")
      (node (ref "IC3") (pin "9") (pinfunction "TS_9") (pintype "bidirectional"))
      (node (ref "R17") (pin "2") (pinfunction "P$2_2") (pintype "bidirectional"))
      (node (ref "R18") (pin "1") (pinfunction "P$1_1") (pintype "bidirectional"))
    )
    (net (code "36") (name "TS4") (class "Default")
      (node (ref "IC4") (pin "9") (pinfunction "TS_9") (pintype "bidirectional"))
      (node (ref "R23") (pin "2") (pinfunction "P$2_2") (pintype "bidirectional"))
      (node (ref "R24") (pin "1") (pinfunction "P$1_1") (pintype "bidirectional"))
    )
    (net (code "37") (name "VBAT") (class "Default")
      (node (ref "C2") (pin "2") (pinfunction "P$2_2") (pintype "bidirectional"))
      (node (ref "IC2") (pin "10") (pinfunction "BAT_10") (pintype "bidirectional"))
      (node (ref "JST1") (pin "1") (pinfunction "S_1") (pintype "passive"))
      (node (ref "U$2") (pin "POS") (pinfunction "+_POS") (pintype "passive"))
    )
    (net (code "38") (name "VBAT2") (class "Default")
      (node (ref "C5") (pin "2") (pinfunction "P$2_2") (pintype "bidirectional"))
      (node (ref "IC1") (pin "10") (pinfunction "BAT_10") (pintype "bidirectional"))
      (node (ref "JST3") (pin "1") (pinfunction "S_1") (pintype "passive"))
      (node (ref "U$1") (pin "POS") (pinfunction "+_POS") (pintype "passive"))
    )
    (net (code "39") (name "VBAT3") (class "Default")
      (node (ref "C8") (pin "2") (pinfunction "P$2_2") (pintype "bidirectional"))
      (node (ref "IC3") (pin "10") (pinfunction "BAT_10") (pintype "bidirectional"))
      (node (ref "JST2") (pin "1") (pinfunction "S_1") (pintype "passive"))
      (node (ref "U$3") (pin "POS") (pinfunction "+_POS") (pintype "passive"))
    )
    (net (code "40") (name "VBAT4") (class "Default")
      (node (ref "C11") (pin "2") (pinfunction "P$2_2") (pintype "bidirectional"))
      (node (ref "IC4") (pin "10") (pinfunction "BAT_10") (pintype "bidirectional"))
      (node (ref "JST4") (pin "1") (pinfunction "S_1") (pintype "passive"))
      (node (ref "U$4") (pin "POS") (pinfunction "+_POS") (pintype "passive"))
    )
    (net (code "41") (name "VUSB") (class "Default")
      (node (ref "C1") (pin "2") (pinfunction "P$2_2") (pintype "bidirectional"))
      (node (ref "C12") (pin "2") (pinfunction "P$2_2") (pintype "bidirectional"))
      (node (ref "C6") (pin "2") (pinfunction "P$2_2") (pintype "bidirectional"))
      (node (ref "C9") (pin "2") (pinfunction "P$2_2") (pintype "bidirectional"))
      (node (ref "D1") (pin "C") (pinfunction "C_C") (pintype "passive"))
      (node (ref "D2") (pin "C") (pinfunction "C_C") (pintype "passive"))
      (node (ref "D3") (pin "C") (pinfunction "C_C") (pintype "passive"))
      (node (ref "IC1") (pin "1") (pinfunction "VIN_1") (pintype "bidirectional"))
      (node (ref "IC1") (pin "4") (pinfunction "EN_4") (pintype "bidirectional"))
      (node (ref "IC2") (pin "1") (pinfunction "VIN_1") (pintype "bidirectional"))
      (node (ref "IC2") (pin "4") (pinfunction "EN_4") (pintype "bidirectional"))
      (node (ref "IC3") (pin "1") (pinfunction "VIN_1") (pintype "bidirectional"))
      (node (ref "IC3") (pin "4") (pinfunction "EN_4") (pintype "bidirectional"))
      (node (ref "IC4") (pin "1") (pinfunction "VIN_1") (pintype "bidirectional"))
      (node (ref "IC4") (pin "4") (pinfunction "EN_4") (pintype "bidirectional"))
      (node (ref "LED1") (pin "A") (pinfunction "A_A") (pintype "passive"))
      (node (ref "LED2") (pin "A") (pinfunction "A_A") (pintype "passive"))
      (node (ref "LED3") (pin "A") (pinfunction "A_A") (pintype "passive"))
      (node (ref "LED4") (pin "A") (pinfunction "A_A") (pintype "passive"))
      (node (ref "LED5") (pin "A") (pinfunction "A_A") (pintype "passive"))
      (node (ref "LED6") (pin "A") (pinfunction "A_A") (pintype "passive"))
      (node (ref "LED7") (pin "A") (pinfunction "A_A") (pintype "passive"))
      (node (ref "LED8") (pin "A") (pinfunction "A_A") (pintype "passive"))
      (node (ref "R12") (pin "2") (pinfunction "P$2_2") (pintype "bidirectional"))
      (node (ref "R18") (pin "2") (pinfunction "P$2_2") (pintype "bidirectional"))
      (node (ref "R24") (pin "2") (pinfunction "P$2_2") (pintype "bidirectional"))
      (node (ref "R5") (pin "2") (pinfunction "P$2_2") (pintype "bidirectional"))
    )
    (net (code "42") (name "unconnected-(U$5-Pad2)") (class "Default")
      (node (ref "U$5") (pin "2") (pinfunction "2_2") (pintype "input"))
    )
    (net (code "43") (name "unconnected-(U$5-Pad3)") (class "Default")
      (node (ref "U$5") (pin "3") (pinfunction "3_3") (pintype "input"))
    )
    (net (code "44") (name "unconnected-(U$5-Pad4)") (class "Default")
      (node (ref "U$5") (pin "4") (pinfunction "4_4") (pintype "input"))
    )
    (net (code "45") (name "unconnected-(U$6-PadNC)") (class "Default")
      (node (ref "U$6") (pin "NC") (pinfunction "NC_NC") (pintype "no_connect"))
    )
    (net (code "46") (name "unconnected-(U$6-PadNC_1)") (class "Default")
      (node (ref "U$6") (pin "NC_1") (pinfunction "NC_1_NC_1") (pintype "no_connect"))
    )
    (net (code "47") (name "unconnected-(X1-Pad2)") (class "Default")
      (node (ref "X1") (pin "2") (pinfunction "2_2") (pintype "input"))
    )
    (net (code "48") (name "unconnected-(X1-Pad3)") (class "Default")
      (node (ref "X1") (pin "3") (pinfunction "3_3") (pintype "input"))
    )
    (net (code "49") (name "unconnected-(X1-Pad4)") (class "Default")
      (node (ref "X1") (pin "4") (pinfunction "4_4") (pintype "input"))
    )
  )
)
